# Farmbot_Rpi_ext.net
KiCad netlist of a schematic drawn in Altium Designer
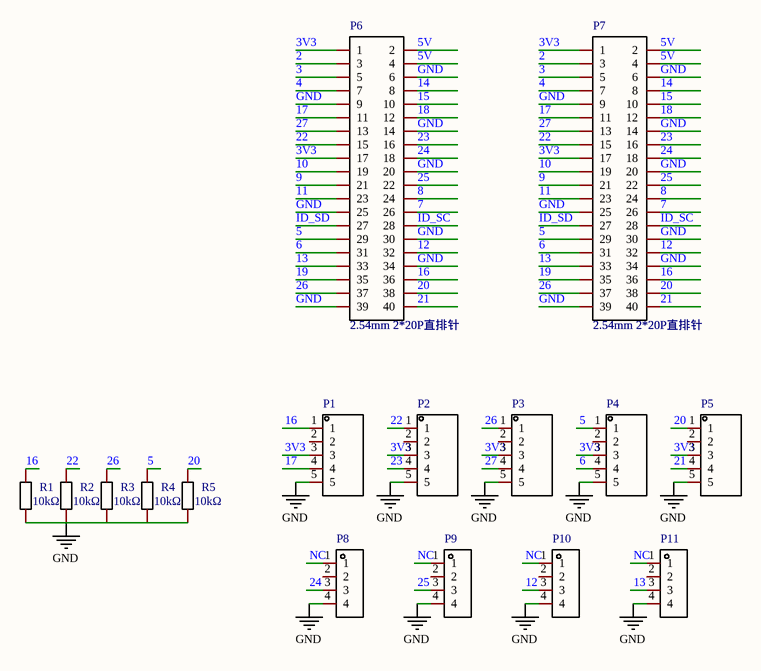
[diagram p0: Farmbot_Rpi_ext.schdoc]

(export (version "E")
  (design (tool "Eeschema 10.0.6"))
  (components
    (comp (ref "P1")
      (value "77311-462K05LF")
      (fields (field (name "MANUFACTURER") "Amphenol"))
      (libsource (lib "altium-import") (part "root_0_77311-462K05LF_"))
    )
    (comp (ref "P2")
      (value "77311-462K05LF")
      (fields (field (name "MANUFACTURER") "Amphenol"))
      (libsource (lib "altium-import") (part "root_0_77311-462K05LF_"))
    )
    (comp (ref "P3")
      (value "77311-462K05LF")
      (fields (field (name "MANUFACTURER") "Amphenol"))
      (libsource (lib "altium-import") (part "root_0_77311-462K05LF_"))
    )
    (comp (ref "P4")
      (value "77311-462K05LF")
      (fields (field (name "MANUFACTURER") "Amphenol"))
      (libsource (lib "altium-import") (part "root_0_77311-462K05LF_"))
    )
    (comp (ref "P5")
      (value "77311-462K05LF")
      (fields (field (name "MANUFACTURER") "Amphenol"))
      (libsource (lib "altium-import") (part "root_0_77311-462K05LF_"))
    )
    (comp (ref "P6")
      (value "2.54mm 2*20P直排针")
      (fields (field (name "NAME") "2.54mm 2*20P直排针") (field (name "MANUFACTURER") "BOOMELE(博穆精密)"))
      (libsource (lib "altium-import") (part "root_0_2.54mm 2*20P直排针_"))
    )
    (comp (ref "P7")
      (value "2.54mm 2*20P直排针")
      (fields (field (name "NAME") "2.54mm 2*20P直排针") (field (name "MANUFACTURER") "BOOMELE(博穆精密)"))
      (libsource (lib "altium-import") (part "root_0_2.54mm 2*20P直排针_"))
    )
    (comp (ref "P8")
      (value "HDR2.54-LI-2x4P")
      (libsource (lib "altium-import") (part "root_0_HDR2.54-LI-2x4P_"))
    )
    (comp (ref "P9")
      (value "HDR2.54-LI-2x4P")
      (libsource (lib "altium-import") (part "root_0_HDR2.54-LI-2x4P_"))
    )
    (comp (ref "P10")
      (value "HDR2.54-LI-2x4P")
      (libsource (lib "altium-import") (part "root_0_HDR2.54-LI-2x4P_"))
    )
    (comp (ref "P11")
      (value "HDR2.54-LI-2x4P")
      (libsource (lib "altium-import") (part "root_0_HDR2.54-LI-2x4P_"))
    )
    (comp (ref "R1")
      (value "10kΩ")
      (fields
        (field (name "MANUFACTURER") "Tyohm(幸亚电阻)")
        (field (name "MANUFACTURER PART") "RMC060310K5%N")
        (field (name "TOLERANCE") "±5%")
      )
      (libsource (lib "altium-import") (part "root_1_RMC060310K5%N_"))
    )
    (comp (ref "R2")
      (value "10kΩ")
      (fields
        (field (name "MANUFACTURER") "Tyohm(幸亚电阻)")
        (field (name "MANUFACTURER PART") "RMC060310K5%N")
        (field (name "TOLERANCE") "±5%")
      )
      (libsource (lib "altium-import") (part "root_1_RMC060310K5%N_"))
    )
    (comp (ref "R3")
      (value "10kΩ")
      (fields
        (field (name "MANUFACTURER") "Tyohm(幸亚电阻)")
        (field (name "MANUFACTURER PART") "RMC060310K5%N")
        (field (name "TOLERANCE") "±5%")
      )
      (libsource (lib "altium-import") (part "root_1_RMC060310K5%N_"))
    )
    (comp (ref "R4")
      (value "10kΩ")
      (fields
        (field (name "MANUFACTURER") "Tyohm(幸亚电阻)")
        (field (name "MANUFACTURER PART") "RMC060310K5%N")
        (field (name "TOLERANCE") "±5%")
      )
      (libsource (lib "altium-import") (part "root_1_RMC060310K5%N_"))
    )
    (comp (ref "R5")
      (value "10kΩ")
      (fields
        (field (name "MANUFACTURER") "Tyohm(幸亚电阻)")
        (field (name "MANUFACTURER PART") "RMC060310K5%N")
        (field (name "TOLERANCE") "±5%")
      )
      (libsource (lib "altium-import") (part "root_1_RMC060310K5%N_"))
    )
  )
  (nets
    (net (code "1") (name "/2") (class "Default")
      (node (ref "P6") (pin "3") (pinfunction "3_3") (pintype "passive"))
      (node (ref "P7") (pin "3") (pinfunction "3_3") (pintype "passive"))
    )
    (net (code "2") (name "/3") (class "Default")
      (node (ref "P6") (pin "5") (pinfunction "5_5") (pintype "passive"))
      (node (ref "P7") (pin "5") (pinfunction "5_5") (pintype "passive"))
    )
    (net (code "3") (name "/3V3") (class "Default")
      (node (ref "P1") (pin "3") (pinfunction "3_3") (pintype "passive"))
      (node (ref "P2") (pin "3") (pinfunction "3_3") (pintype "passive"))
      (node (ref "P3") (pin "3") (pinfunction "3_3") (pintype "passive"))
      (node (ref "P4") (pin "3") (pinfunction "3_3") (pintype "passive"))
      (node (ref "P5") (pin "3") (pinfunction "3_3") (pintype "passive"))
      (node (ref "P6") (pin "1") (pinfunction "1_1") (pintype "passive"))
      (node (ref "P6") (pin "17") (pinfunction "17_17") (pintype "passive"))
      (node (ref "P7") (pin "1") (pinfunction "1_1") (pintype "passive"))
      (node (ref "P7") (pin "17") (pinfunction "17_17") (pintype "passive"))
    )
    (net (code "4") (name "/4") (class "Default")
      (node (ref "P6") (pin "7") (pinfunction "7_7") (pintype "passive"))
      (node (ref "P7") (pin "7") (pinfunction "7_7") (pintype "passive"))
    )
    (net (code "5") (name "/5") (class "Default")
      (node (ref "P4") (pin "1") (pinfunction "1_1") (pintype "passive"))
      (node (ref "P6") (pin "29") (pinfunction "29_29") (pintype "passive"))
      (node (ref "P7") (pin "29") (pinfunction "29_29") (pintype "passive"))
      (node (ref "R4") (pin "2") (pinfunction "2_2") (pintype "passive"))
    )
    (net (code "6") (name "/5V") (class "Default")
      (node (ref "P6") (pin "2") (pinfunction "2_2") (pintype "passive"))
      (node (ref "P6") (pin "4") (pinfunction "4_4") (pintype "passive"))
      (node (ref "P7") (pin "2") (pinfunction "2_2") (pintype "passive"))
      (node (ref "P7") (pin "4") (pinfunction "4_4") (pintype "passive"))
    )
    (net (code "7") (name "/6") (class "Default")
      (node (ref "P4") (pin "4") (pinfunction "4_4") (pintype "passive"))
      (node (ref "P6") (pin "31") (pinfunction "31_31") (pintype "passive"))
      (node (ref "P7") (pin "31") (pinfunction "31_31") (pintype "passive"))
    )
    (net (code "8") (name "/7") (class "Default")
      (node (ref "P6") (pin "26") (pinfunction "26_26") (pintype "passive"))
      (node (ref "P7") (pin "26") (pinfunction "26_26") (pintype "passive"))
    )
    (net (code "9") (name "/8") (class "Default")
      (node (ref "P6") (pin "24") (pinfunction "24_24") (pintype "passive"))
      (node (ref "P7") (pin "24") (pinfunction "24_24") (pintype "passive"))
    )
    (net (code "10") (name "/9") (class "Default")
      (node (ref "P6") (pin "21") (pinfunction "21_21") (pintype "passive"))
      (node (ref "P7") (pin "21") (pinfunction "21_21") (pintype "passive"))
    )
    (net (code "11") (name "/10") (class "Default")
      (node (ref "P6") (pin "19") (pinfunction "19_19") (pintype "passive"))
      (node (ref "P7") (pin "19") (pinfunction "19_19") (pintype "passive"))
    )
    (net (code "12") (name "/11") (class "Default")
      (node (ref "P6") (pin "23") (pinfunction "23_23") (pintype "passive"))
      (node (ref "P7") (pin "23") (pinfunction "23_23") (pintype "passive"))
    )
    (net (code "13") (name "/12") (class "Default")
      (node (ref "P10") (pin "3") (pinfunction "3_3") (pintype "passive"))
      (node (ref "P6") (pin "32") (pinfunction "32_32") (pintype "passive"))
      (node (ref "P7") (pin "32") (pinfunction "32_32") (pintype "passive"))
    )
    (net (code "14") (name "/13") (class "Default")
      (node (ref "P11") (pin "3") (pinfunction "3_3") (pintype "passive"))
      (node (ref "P6") (pin "33") (pinfunction "33_33") (pintype "passive"))
      (node (ref "P7") (pin "33") (pinfunction "33_33") (pintype "passive"))
    )
    (net (code "15") (name "/14") (class "Default")
      (node (ref "P6") (pin "8") (pinfunction "8_8") (pintype "passive"))
      (node (ref "P7") (pin "8") (pinfunction "8_8") (pintype "passive"))
    )
    (net (code "16") (name "/15") (class "Default")
      (node (ref "P6") (pin "10") (pinfunction "10_10") (pintype "passive"))
      (node (ref "P7") (pin "10") (pinfunction "10_10") (pintype "passive"))
    )
    (net (code "17") (name "/16") (class "Default")
      (node (ref "P1") (pin "1") (pinfunction "1_1") (pintype "passive"))
      (node (ref "P6") (pin "36") (pinfunction "36_36") (pintype "passive"))
      (node (ref "P7") (pin "36") (pinfunction "36_36") (pintype "passive"))
      (node (ref "R1") (pin "2") (pinfunction "2_2") (pintype "passive"))
    )
    (net (code "18") (name "/17") (class "Default")
      (node (ref "P1") (pin "4") (pinfunction "4_4") (pintype "passive"))
      (node (ref "P6") (pin "11") (pinfunction "11_11") (pintype "passive"))
      (node (ref "P7") (pin "11") (pinfunction "11_11") (pintype "passive"))
    )
    (net (code "19") (name "/18") (class "Default")
      (node (ref "P6") (pin "12") (pinfunction "12_12") (pintype "passive"))
      (node (ref "P7") (pin "12") (pinfunction "12_12") (pintype "passive"))
    )
    (net (code "20") (name "/19") (class "Default")
      (node (ref "P6") (pin "35") (pinfunction "35_35") (pintype "passive"))
      (node (ref "P7") (pin "35") (pinfunction "35_35") (pintype "passive"))
    )
    (net (code "21") (name "/20") (class "Default")
      (node (ref "P5") (pin "1") (pinfunction "1_1") (pintype "passive"))
      (node (ref "P6") (pin "38") (pinfunction "38_38") (pintype "passive"))
      (node (ref "P7") (pin "38") (pinfunction "38_38") (pintype "passive"))
      (node (ref "R5") (pin "2") (pinfunction "2_2") (pintype "passive"))
    )
    (net (code "22") (name "/21") (class "Default")
      (node (ref "P5") (pin "4") (pinfunction "4_4") (pintype "passive"))
      (node (ref "P6") (pin "40") (pinfunction "40_40") (pintype "passive"))
      (node (ref "P7") (pin "40") (pinfunction "40_40") (pintype "passive"))
    )
    (net (code "23") (name "/22") (class "Default")
      (node (ref "P2") (pin "1") (pinfunction "1_1") (pintype "passive"))
      (node (ref "P6") (pin "15") (pinfunction "15_15") (pintype "passive"))
      (node (ref "P7") (pin "15") (pinfunction "15_15") (pintype "passive"))
      (node (ref "R2") (pin "2") (pinfunction "2_2") (pintype "passive"))
    )
    (net (code "24") (name "/23") (class "Default")
      (node (ref "P2") (pin "4") (pinfunction "4_4") (pintype "passive"))
      (node (ref "P6") (pin "16") (pinfunction "16_16") (pintype "passive"))
      (node (ref "P7") (pin "16") (pinfunction "16_16") (pintype "passive"))
    )
    (net (code "25") (name "/24") (class "Default")
      (node (ref "P6") (pin "18") (pinfunction "18_18") (pintype "passive"))
      (node (ref "P7") (pin "18") (pinfunction "18_18") (pintype "passive"))
      (node (ref "P8") (pin "3") (pinfunction "3_3") (pintype "passive"))
    )
    (net (code "26") (name "/25") (class "Default")
      (node (ref "P6") (pin "22") (pinfunction "22_22") (pintype "passive"))
      (node (ref "P7") (pin "22") (pinfunction "22_22") (pintype "passive"))
      (node (ref "P9") (pin "3") (pinfunction "3_3") (pintype "passive"))
    )
    (net (code "27") (name "/26") (class "Default")
      (node (ref "P3") (pin "1") (pinfunction "1_1") (pintype "passive"))
      (node (ref "P6") (pin "37") (pinfunction "37_37") (pintype "passive"))
      (node (ref "P7") (pin "37") (pinfunction "37_37") (pintype "passive"))
      (node (ref "R3") (pin "2") (pinfunction "2_2") (pintype "passive"))
    )
    (net (code "28") (name "/27") (class "Default")
      (node (ref "P3") (pin "4") (pinfunction "4_4") (pintype "passive"))
      (node (ref "P6") (pin "13") (pinfunction "13_13") (pintype "passive"))
      (node (ref "P7") (pin "13") (pinfunction "13_13") (pintype "passive"))
    )
    (net (code "29") (name "/ID_SC") (class "Default")
      (node (ref "P6") (pin "28") (pinfunction "28_28") (pintype "passive"))
      (node (ref "P7") (pin "28") (pinfunction "28_28") (pintype "passive"))
    )
    (net (code "30") (name "/ID_SD") (class "Default")
      (node (ref "P6") (pin "27") (pinfunction "27_27") (pintype "passive"))
      (node (ref "P7") (pin "27") (pinfunction "27_27") (pintype "passive"))
    )
    (net (code "31") (name "/NC") (class "Default")
      (node (ref "P10") (pin "1") (pinfunction "1_1") (pintype "passive"))
      (node (ref "P11") (pin "1") (pinfunction "1_1") (pintype "passive"))
      (node (ref "P8") (pin "1") (pinfunction "1_1") (pintype "passive"))
      (node (ref "P9") (pin "1") (pinfunction "1_1") (pintype "passive"))
    )
    (net (code "32") (name "GND") (class "Default")
      (node (ref "P1") (pin "5") (pinfunction "5_5") (pintype "passive"))
      (node (ref "P10") (pin "4") (pinfunction "4_4") (pintype "passive"))
      (node (ref "P11") (pin "4") (pinfunction "4_4") (pintype "passive"))
      (node (ref "P2") (pin "5") (pinfunction "5_5") (pintype "passive"))
      (node (ref "P3") (pin "5") (pinfunction "5_5") (pintype "passive"))
      (node (ref "P4") (pin "5") (pinfunction "5_5") (pintype "passive"))
      (node (ref "P5") (pin "5") (pinfunction "5_5") (pintype "passive"))
      (node (ref "P6") (pin "14") (pinfunction "14_14") (pintype "passive"))
      (node (ref "P6") (pin "20") (pinfunction "20_20") (pintype "passive"))
      (node (ref "P6") (pin "25") (pinfunction "25_25") (pintype "passive"))
      (node (ref "P6") (pin "30") (pinfunction "30_30") (pintype "passive"))
      (node (ref "P6") (pin "34") (pinfunction "34_34") (pintype "passive"))
      (node (ref "P6") (pin "39") (pinfunction "39_39") (pintype "passive"))
      (node (ref "P6") (pin "6") (pinfunction "6_6") (pintype "passive"))
      (node (ref "P6") (pin "9") (pinfunction "9_9") (pintype "passive"))
      (node (ref "P7") (pin "14") (pinfunction "14_14") (pintype "passive"))
      (node (ref "P7") (pin "20") (pinfunction "20_20") (pintype "passive"))
      (node (ref "P7") (pin "25") (pinfunction "25_25") (pintype "passive"))
      (node (ref "P7") (pin "30") (pinfunction "30_30") (pintype "passive"))
      (node (ref "P7") (pin "34") (pinfunction "34_34") (pintype "passive"))
      (node (ref "P7") (pin "39") (pinfunction "39_39") (pintype "passive"))
      (node (ref "P7") (pin "6") (pinfunction "6_6") (pintype "passive"))
      (node (ref "P7") (pin "9") (pinfunction "9_9") (pintype "passive"))
      (node (ref "P8") (pin "4") (pinfunction "4_4") (pintype "passive"))
      (node (ref "P9") (pin "4") (pinfunction "4_4") (pintype "passive"))
      (node (ref "R1") (pin "1") (pinfunction "1_1") (pintype "passive"))
      (node (ref "R2") (pin "1") (pinfunction "1_1") (pintype "passive"))
      (node (ref "R3") (pin "1") (pinfunction "1_1") (pintype "passive"))
      (node (ref "R4") (pin "1") (pinfunction "1_1") (pintype "passive"))
      (node (ref "R5") (pin "1") (pinfunction "1_1") (pintype "passive"))
    )
    (net (code "33") (name "unconnected-(P1-Pad2)") (class "Default")
      (node (ref "P1") (pin "2") (pinfunction "2_2") (pintype "passive"))
    )
    (net (code "34") (name "unconnected-(P2-Pad2)") (class "Default")
      (node (ref "P2") (pin "2") (pinfunction "2_2") (pintype "passive"))
    )
    (net (code "35") (name "unconnected-(P3-Pad2)") (class "Default")
      (node (ref "P3") (pin "2") (pinfunction "2_2") (pintype "passive"))
    )
    (net (code "36") (name "unconnected-(P4-Pad2)") (class "Default")
      (node (ref "P4") (pin "2") (pinfunction "2_2") (pintype "passive"))
    )
    (net (code "37") (name "unconnected-(P5-Pad2)") (class "Default")
      (node (ref "P5") (pin "2") (pinfunction "2_2") (pintype "passive"))
    )
    (net (code "38") (name "unconnected-(P8-Pad2)") (class "Default")
      (node (ref "P8") (pin "2") (pinfunction "2_2") (pintype "passive"))
    )
    (net (code "39") (name "unconnected-(P9-Pad2)") (class "Default")
      (node (ref "P9") (pin "2") (pinfunction "2_2") (pintype "passive"))
    )
    (net (code "40") (name "unconnected-(P10-Pad2)") (class "Default")
      (node (ref "P10") (pin "2") (pinfunction "2_2") (pintype "passive"))
    )
    (net (code "41") (name "unconnected-(P11-Pad2)") (class "Default")
      (node (ref "P11") (pin "2") (pinfunction "2_2") (pintype "passive"))
    )
  )
)
